# M7821.net
KiCad netlist of a schematic drawn in EAGLE
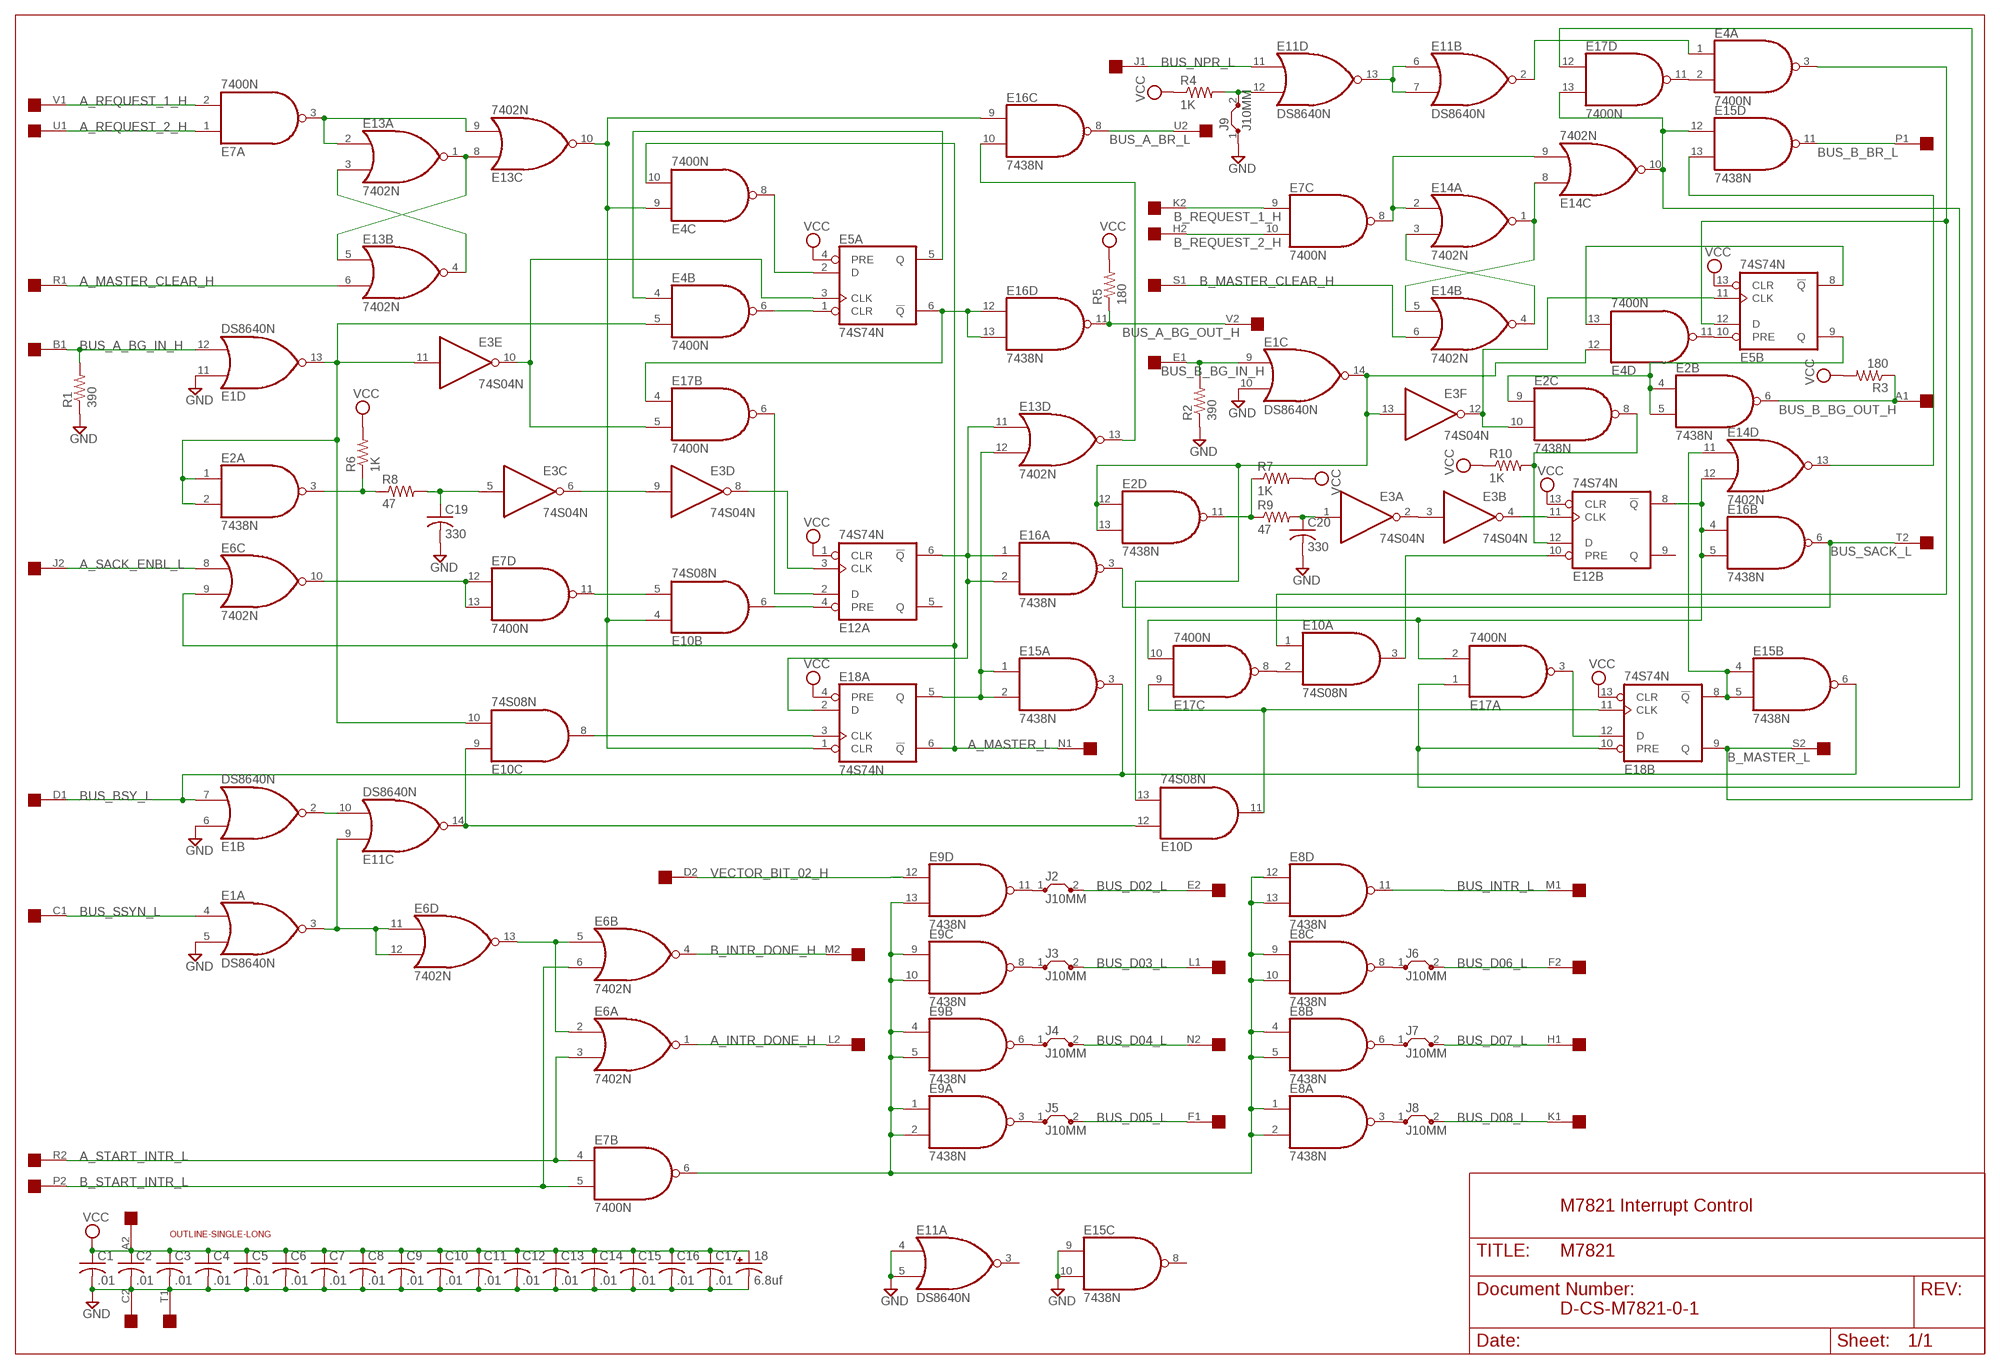
[diagram p0: schematic, sheet 1]

(export (version "E")
  (design (tool "Eeschema 10.0.6"))
  (components
    (comp (ref "18")
      (value "6.8uf")
      (footprint "eagle-import:E15-5")
      (libsource (lib "eagle-import") (part "CPOL-USE15-5AXIAL"))
    )
    (comp (ref "C1")
      (value ".01")
      (footprint "eagle-import:C050-025X075")
      (libsource (lib "eagle-import") (part "C-US050-025X075"))
    )
    (comp (ref "C2")
      (value ".01")
      (footprint "eagle-import:C050-025X075")
      (libsource (lib "eagle-import") (part "C-US050-025X075"))
    )
    (comp (ref "C3")
      (value ".01")
      (footprint "eagle-import:C050-025X075")
      (libsource (lib "eagle-import") (part "C-US050-025X075"))
    )
    (comp (ref "C4")
      (value ".01")
      (footprint "eagle-import:C050-025X075")
      (libsource (lib "eagle-import") (part "C-US050-025X075"))
    )
    (comp (ref "C5")
      (value ".01")
      (footprint "eagle-import:C050-025X075")
      (libsource (lib "eagle-import") (part "C-US050-025X075"))
    )
    (comp (ref "C6")
      (value ".01")
      (footprint "eagle-import:C050-025X075")
      (libsource (lib "eagle-import") (part "C-US050-025X075"))
    )
    (comp (ref "C7")
      (value ".01")
      (footprint "eagle-import:C050-025X075")
      (libsource (lib "eagle-import") (part "C-US050-025X075"))
    )
    (comp (ref "C8")
      (value ".01")
      (footprint "eagle-import:C050-025X075")
      (libsource (lib "eagle-import") (part "C-US050-025X075"))
    )
    (comp (ref "C9")
      (value ".01")
      (footprint "eagle-import:C050-025X075")
      (libsource (lib "eagle-import") (part "C-US050-025X075"))
    )
    (comp (ref "C10")
      (value ".01")
      (footprint "eagle-import:C050-025X075")
      (libsource (lib "eagle-import") (part "C-US050-025X075"))
    )
    (comp (ref "C11")
      (value ".01")
      (footprint "eagle-import:C050-025X075")
      (libsource (lib "eagle-import") (part "C-US050-025X075"))
    )
    (comp (ref "C12")
      (value ".01")
      (footprint "eagle-import:C050-025X075")
      (libsource (lib "eagle-import") (part "C-US050-025X075"))
    )
    (comp (ref "C13")
      (value ".01")
      (footprint "eagle-import:C050-025X075")
      (libsource (lib "eagle-import") (part "C-US050-025X075"))
    )
    (comp (ref "C14")
      (value ".01")
      (footprint "eagle-import:C050-025X075")
      (libsource (lib "eagle-import") (part "C-US050-025X075"))
    )
    (comp (ref "C15")
      (value ".01")
      (footprint "eagle-import:C050-025X075")
      (libsource (lib "eagle-import") (part "C-US050-025X075"))
    )
    (comp (ref "C16")
      (value ".01")
      (footprint "eagle-import:C050-025X075")
      (libsource (lib "eagle-import") (part "C-US050-025X075"))
    )
    (comp (ref "C17")
      (value ".01")
      (footprint "eagle-import:C050-025X075")
      (libsource (lib "eagle-import") (part "C-US050-025X075"))
    )
    (comp (ref "C19")
      (value "330")
      (footprint "eagle-import:C050-025X075")
      (libsource (lib "eagle-import") (part "C-US050-025X075"))
    )
    (comp (ref "C20")
      (value "330")
      (footprint "eagle-import:C050-025X075")
      (libsource (lib "eagle-import") (part "C-US050-025X075"))
    )
    (comp (ref "E1")
      (value "DS8640N")
      (footprint "eagle-import:DIL14")
      (libsource (lib "eagle-import") (part "DS8640N"))
    )
    (comp (ref "E2")
      (value "7438N")
      (footprint "eagle-import:DIL14")
      (libsource (lib "eagle-import") (part "7438N"))
    )
    (comp (ref "E3")
      (value "74S04N")
      (footprint "eagle-import:DIL14")
      (libsource (lib "eagle-import") (part "7404NS"))
    )
    (comp (ref "E4")
      (value "7400N")
      (footprint "eagle-import:DIL14")
      (libsource (lib "eagle-import") (part "7400N"))
    )
    (comp (ref "E5")
      (value "74S74N")
      (footprint "eagle-import:DIL14")
      (libsource (lib "eagle-import") (part "7474NS"))
    )
    (comp (ref "E6")
      (value "7402N")
      (footprint "eagle-import:DIL14")
      (libsource (lib "eagle-import") (part "7402N"))
    )
    (comp (ref "E7")
      (value "7400N")
      (footprint "eagle-import:DIL14")
      (libsource (lib "eagle-import") (part "7400N"))
    )
    (comp (ref "E8")
      (value "7438N")
      (footprint "eagle-import:DIL14")
      (libsource (lib "eagle-import") (part "7438N"))
    )
    (comp (ref "E9")
      (value "7438N")
      (footprint "eagle-import:DIL14")
      (libsource (lib "eagle-import") (part "7438N"))
    )
    (comp (ref "E10")
      (value "74S08N")
      (footprint "eagle-import:DIL14")
      (libsource (lib "eagle-import") (part "7408NS"))
    )
    (comp (ref "E11")
      (value "DS8640N")
      (footprint "eagle-import:DIL14")
      (libsource (lib "eagle-import") (part "DS8640N"))
    )
    (comp (ref "E12")
      (value "74S74N")
      (footprint "eagle-import:DIL14")
      (libsource (lib "eagle-import") (part "7474NS"))
    )
    (comp (ref "E13")
      (value "7402N")
      (footprint "eagle-import:DIL14")
      (libsource (lib "eagle-import") (part "7402N"))
    )
    (comp (ref "E14")
      (value "7402N")
      (footprint "eagle-import:DIL14")
      (libsource (lib "eagle-import") (part "7402N"))
    )
    (comp (ref "E15")
      (value "7438N")
      (footprint "eagle-import:DIL14")
      (libsource (lib "eagle-import") (part "7438N"))
    )
    (comp (ref "E16")
      (value "7438N")
      (footprint "eagle-import:DIL14")
      (libsource (lib "eagle-import") (part "7438N"))
    )
    (comp (ref "E17")
      (value "7400N")
      (footprint "eagle-import:DIL14")
      (libsource (lib "eagle-import") (part "7400N"))
    )
    (comp (ref "E18")
      (value "74S74N")
      (footprint "eagle-import:DIL14")
      (libsource (lib "eagle-import") (part "7474NS"))
    )
    (comp (ref "J2")
      (value "J10MM")
      (footprint "eagle-import:10")
      (libsource (lib "eagle-import") (part "J10MM"))
    )
    (comp (ref "J3")
      (value "J10MM")
      (footprint "eagle-import:10")
      (libsource (lib "eagle-import") (part "J10MM"))
    )
    (comp (ref "J4")
      (value "J10MM")
      (footprint "eagle-import:10")
      (libsource (lib "eagle-import") (part "J10MM"))
    )
    (comp (ref "J5")
      (value "J10MM")
      (footprint "eagle-import:10")
      (libsource (lib "eagle-import") (part "J10MM"))
    )
    (comp (ref "J6")
      (value "J10MM")
      (footprint "eagle-import:10")
      (libsource (lib "eagle-import") (part "J10MM"))
    )
    (comp (ref "J7")
      (value "J10MM")
      (footprint "eagle-import:10")
      (libsource (lib "eagle-import") (part "J10MM"))
    )
    (comp (ref "J8")
      (value "J10MM")
      (footprint "eagle-import:10")
      (libsource (lib "eagle-import") (part "J10MM"))
    )
    (comp (ref "J9")
      (value "J10MM")
      (footprint "eagle-import:10")
      (libsource (lib "eagle-import") (part "J10MM"))
    )
    (comp (ref "R1")
      (value "390")
      (footprint "eagle-import:0207_10")
      (libsource (lib "eagle-import") (part "R-US_0207/10"))
    )
    (comp (ref "R2")
      (value "390")
      (footprint "eagle-import:0207_10")
      (libsource (lib "eagle-import") (part "R-US_0207/10"))
    )
    (comp (ref "R3")
      (value "180")
      (footprint "eagle-import:0207_10")
      (libsource (lib "eagle-import") (part "R-US_0207/10"))
    )
    (comp (ref "R4")
      (value "1K")
      (footprint "eagle-import:0207_10")
      (libsource (lib "eagle-import") (part "R-US_0207/10"))
    )
    (comp (ref "R5")
      (value "180")
      (footprint "eagle-import:0207_10")
      (libsource (lib "eagle-import") (part "R-US_0207/10"))
    )
    (comp (ref "R6")
      (value "1K")
      (footprint "eagle-import:0207_10")
      (libsource (lib "eagle-import") (part "R-US_0207/10"))
    )
    (comp (ref "R7")
      (value "1K")
      (footprint "eagle-import:0207_10")
      (libsource (lib "eagle-import") (part "R-US_0207/10"))
    )
    (comp (ref "R8")
      (value "47")
      (footprint "eagle-import:0207_10")
      (libsource (lib "eagle-import") (part "R-US_0207/10"))
    )
    (comp (ref "R9")
      (value "47")
      (footprint "eagle-import:0207_10")
      (libsource (lib "eagle-import") (part "R-US_0207/10"))
    )
    (comp (ref "R10")
      (value "1K")
      (footprint "eagle-import:0207_10")
      (libsource (lib "eagle-import") (part "R-US_0207/10"))
    )
    (comp (ref "U$1")
      (value "OUTLINE-SINGLE-LONG")
      (footprint "eagle-import:SINGLE-LONG")
      (libsource (lib "eagle-import") (part "OUTLINE-SINGLE-LONG"))
    )
    (comp (ref "U$2")
      (value "SINGLE")
      (footprint "eagle-import:EDGE-CON2")
      (libsource (lib "eagle-import") (part "SINGLE"))
    )
  )
  (nets
    (net (code "1") (name "/A_INTR_DONE_H") (class "Default")
      (node (ref "E6") (pin "1") (pinfunction "O_1") (pintype "output"))
      (node (ref "U$2") (pin "L2") (pinfunction "1_L2") (pintype "bidirectional"))
    )
    (net (code "2") (name "/A_MASTER_CLEAR_H") (class "Default")
      (node (ref "E13") (pin "6") (pinfunction "I1_6") (pintype "input"))
      (node (ref "U$2") (pin "R1") (pinfunction "1_R1") (pintype "bidirectional"))
    )
    (net (code "3") (name "/A_MASTER_L") (class "Default")
      (node (ref "E18") (pin "6") (pinfunction "~{Q}_6") (pintype "output"))
      (node (ref "E4") (pin "10") (pinfunction "I1_10") (pintype "input"))
      (node (ref "E6") (pin "9") (pinfunction "I1_9") (pintype "input"))
      (node (ref "U$2") (pin "N1") (pinfunction "1_N1") (pintype "bidirectional"))
    )
    (net (code "4") (name "/A_REQUEST_1_H") (class "Default")
      (node (ref "E7") (pin "2") (pinfunction "I1_2") (pintype "input"))
      (node (ref "U$2") (pin "V1") (pinfunction "1_V1") (pintype "bidirectional"))
    )
    (net (code "5") (name "/A_REQUEST_2_H") (class "Default")
      (node (ref "E7") (pin "1") (pinfunction "I0_1") (pintype "input"))
      (node (ref "U$2") (pin "U1") (pinfunction "1_U1") (pintype "bidirectional"))
    )
    (net (code "6") (name "/A_SACK_ENBL_L") (class "Default")
      (node (ref "E6") (pin "8") (pinfunction "I0_8") (pintype "input"))
      (node (ref "U$2") (pin "J2") (pinfunction "1_J2") (pintype "bidirectional"))
    )
    (net (code "7") (name "/A_START_INTR_L") (class "Default")
      (node (ref "E6") (pin "3") (pinfunction "I1_3") (pintype "input"))
      (node (ref "E7") (pin "4") (pinfunction "I0_4") (pintype "input"))
      (node (ref "U$2") (pin "R2") (pinfunction "1_R2") (pintype "bidirectional"))
    )
    (net (code "8") (name "/BUS_A_BG_IN_H") (class "Default")
      (node (ref "E1") (pin "12") (pinfunction "I1_12") (pintype "input"))
      (node (ref "R1") (pin "2") (pinfunction "2_2") (pintype "passive"))
      (node (ref "U$2") (pin "B1") (pinfunction "1_B1") (pintype "bidirectional"))
    )
    (net (code "9") (name "/BUS_A_BG_OUT_H") (class "Default")
      (node (ref "E16") (pin "11") (pinfunction "O_11") (pintype "open_collector"))
      (node (ref "R5") (pin "1") (pinfunction "1_1") (pintype "passive"))
      (node (ref "U$2") (pin "V2") (pinfunction "1_V2") (pintype "bidirectional"))
    )
    (net (code "10") (name "/BUS_A_BR_L") (class "Default")
      (node (ref "E16") (pin "8") (pinfunction "O_8") (pintype "open_collector"))
      (node (ref "U$2") (pin "U2") (pinfunction "1_U2") (pintype "bidirectional"))
    )
    (net (code "11") (name "/BUS_BSY_L") (class "Default")
      (node (ref "E1") (pin "7") (pinfunction "I1_7") (pintype "input"))
      (node (ref "E15") (pin "3") (pinfunction "O_3") (pintype "open_collector"))
      (node (ref "E15") (pin "6") (pinfunction "O_6") (pintype "open_collector"))
      (node (ref "U$2") (pin "D1") (pinfunction "1_D1") (pintype "bidirectional"))
    )
    (net (code "12") (name "/BUS_B_BG_IN_H") (class "Default")
      (node (ref "E1") (pin "9") (pinfunction "I0_9") (pintype "input"))
      (node (ref "R2") (pin "2") (pinfunction "2_2") (pintype "passive"))
      (node (ref "U$2") (pin "E1") (pinfunction "1_E1") (pintype "bidirectional"))
    )
    (net (code "13") (name "/BUS_B_BG_OUT_H") (class "Default")
      (node (ref "E2") (pin "6") (pinfunction "O_6") (pintype "open_collector"))
      (node (ref "R3") (pin "1") (pinfunction "1_1") (pintype "passive"))
      (node (ref "U$2") (pin "A1") (pinfunction "1_A1") (pintype "bidirectional"))
    )
    (net (code "14") (name "/BUS_B_BR_L") (class "Default")
      (node (ref "E15") (pin "11") (pinfunction "O_11") (pintype "open_collector"))
      (node (ref "U$2") (pin "P1") (pinfunction "1_P1") (pintype "bidirectional"))
    )
    (net (code "15") (name "/BUS_D02_L") (class "Default")
      (node (ref "J2") (pin "2") (pinfunction "2_2") (pintype "passive"))
      (node (ref "U$2") (pin "E2") (pinfunction "1_E2") (pintype "bidirectional"))
    )
    (net (code "16") (name "/BUS_D03_L") (class "Default")
      (node (ref "J3") (pin "2") (pinfunction "2_2") (pintype "passive"))
      (node (ref "U$2") (pin "L1") (pinfunction "1_L1") (pintype "bidirectional"))
    )
    (net (code "17") (name "/BUS_D04_L") (class "Default")
      (node (ref "J4") (pin "2") (pinfunction "2_2") (pintype "passive"))
      (node (ref "U$2") (pin "N2") (pinfunction "1_N2") (pintype "bidirectional"))
    )
    (net (code "18") (name "/BUS_D05_L") (class "Default")
      (node (ref "J5") (pin "2") (pinfunction "2_2") (pintype "passive"))
      (node (ref "U$2") (pin "F1") (pinfunction "1_F1") (pintype "bidirectional"))
    )
    (net (code "19") (name "/BUS_D06_L") (class "Default")
      (node (ref "J6") (pin "2") (pinfunction "2_2") (pintype "passive"))
      (node (ref "U$2") (pin "F2") (pinfunction "1_F2") (pintype "bidirectional"))
    )
    (net (code "20") (name "/BUS_D07_L") (class "Default")
      (node (ref "J7") (pin "2") (pinfunction "2_2") (pintype "passive"))
      (node (ref "U$2") (pin "H1") (pinfunction "1_H1") (pintype "bidirectional"))
    )
    (net (code "21") (name "/BUS_D08_L") (class "Default")
      (node (ref "J8") (pin "2") (pinfunction "2_2") (pintype "passive"))
      (node (ref "U$2") (pin "K1") (pinfunction "1_K1") (pintype "bidirectional"))
    )
    (net (code "22") (name "/BUS_INTR_L") (class "Default")
      (node (ref "E8") (pin "11") (pinfunction "O_11") (pintype "open_collector"))
      (node (ref "U$2") (pin "M1") (pinfunction "1_M1") (pintype "bidirectional"))
    )
    (net (code "23") (name "/BUS_NPR_L") (class "Default")
      (node (ref "E11") (pin "11") (pinfunction "I0_11") (pintype "input"))
      (node (ref "U$2") (pin "J1") (pinfunction "1_J1") (pintype "bidirectional"))
    )
    (net (code "24") (name "/BUS_SACK_L") (class "Default")
      (node (ref "E16") (pin "3") (pinfunction "O_3") (pintype "open_collector"))
      (node (ref "E16") (pin "6") (pinfunction "O_6") (pintype "open_collector"))
      (node (ref "U$2") (pin "T2") (pinfunction "1_T2") (pintype "bidirectional"))
    )
    (net (code "25") (name "/BUS_SSYN_L") (class "Default")
      (node (ref "E1") (pin "4") (pinfunction "I0_4") (pintype "input"))
      (node (ref "U$2") (pin "C1") (pinfunction "1_C1") (pintype "bidirectional"))
    )
    (net (code "26") (name "/B_INTR_DONE_H") (class "Default")
      (node (ref "E6") (pin "4") (pinfunction "O_4") (pintype "output"))
      (node (ref "U$2") (pin "M2") (pinfunction "1_M2") (pintype "bidirectional"))
    )
    (net (code "27") (name "/B_MASTER_CLEAR_H") (class "Default")
      (node (ref "E14") (pin "6") (pinfunction "I1_6") (pintype "input"))
      (node (ref "U$2") (pin "S1") (pinfunction "1_S1") (pintype "bidirectional"))
    )
    (net (code "28") (name "/B_MASTER_L") (class "Default")
      (node (ref "E17") (pin "12") (pinfunction "I0_12") (pintype "input"))
      (node (ref "E18") (pin "9") (pinfunction "Q_9") (pintype "output"))
      (node (ref "U$2") (pin "S2") (pinfunction "1_S2") (pintype "bidirectional"))
    )
    (net (code "29") (name "/B_REQUEST_1_H") (class "Default")
      (node (ref "E7") (pin "9") (pinfunction "I0_9") (pintype "input"))
      (node (ref "U$2") (pin "K2") (pinfunction "1_K2") (pintype "bidirectional"))
    )
    (net (code "30") (name "/B_REQUEST_2_H") (class "Default")
      (node (ref "E7") (pin "10") (pinfunction "I1_10") (pintype "input"))
      (node (ref "U$2") (pin "H2") (pinfunction "1_H2") (pintype "bidirectional"))
    )
    (net (code "31") (name "/B_START_INTR_L") (class "Default")
      (node (ref "E6") (pin "6") (pinfunction "I1_6") (pintype "input"))
      (node (ref "E7") (pin "5") (pinfunction "I1_5") (pintype "input"))
      (node (ref "U$2") (pin "P2") (pinfunction "1_P2") (pintype "bidirectional"))
    )
    (net (code "32") (name "/VECTOR_BIT_02_H") (class "Default")
      (node (ref "E9") (pin "12") (pinfunction "I0_12") (pintype "input"))
      (node (ref "U$2") (pin "D2") (pinfunction "1_D2") (pintype "bidirectional"))
    )
    (net (code "33") (name "GND") (class "Default")
      (node (ref "18") (pin "-") (pinfunction "-_-") (pintype "passive"))
      (node (ref "C1") (pin "2") (pinfunction "2_2") (pintype "passive"))
      (node (ref "C10") (pin "2") (pinfunction "2_2") (pintype "passive"))
      (node (ref "C11") (pin "2") (pinfunction "2_2") (pintype "passive"))
      (node (ref "C12") (pin "2") (pinfunction "2_2") (pintype "passive"))
      (node (ref "C13") (pin "2") (pinfunction "2_2") (pintype "passive"))
      (node (ref "C14") (pin "2") (pinfunction "2_2") (pintype "passive"))
      (node (ref "C15") (pin "2") (pinfunction "2_2") (pintype "passive"))
      (node (ref "C16") (pin "2") (pinfunction "2_2") (pintype "passive"))
      (node (ref "C17") (pin "2") (pinfunction "2_2") (pintype "passive"))
      (node (ref "C19") (pin "2") (pinfunction "2_2") (pintype "passive"))
      (node (ref "C2") (pin "2") (pinfunction "2_2") (pintype "passive"))
      (node (ref "C20") (pin "2") (pinfunction "2_2") (pintype "passive"))
      (node (ref "C3") (pin "2") (pinfunction "2_2") (pintype "passive"))
      (node (ref "C4") (pin "2") (pinfunction "2_2") (pintype "passive"))
      (node (ref "C5") (pin "2") (pinfunction "2_2") (pintype "passive"))
      (node (ref "C6") (pin "2") (pinfunction "2_2") (pintype "passive"))
      (node (ref "C7") (pin "2") (pinfunction "2_2") (pintype "passive"))
      (node (ref "C8") (pin "2") (pinfunction "2_2") (pintype "passive"))
      (node (ref "C9") (pin "2") (pinfunction "2_2") (pintype "passive"))
      (node (ref "E1") (pin "10") (pinfunction "I1_10") (pintype "input"))
      (node (ref "E1") (pin "11") (pinfunction "I0_11") (pintype "input"))
      (node (ref "E1") (pin "5") (pinfunction "I1_5") (pintype "input"))
      (node (ref "E1") (pin "6") (pinfunction "I0_6") (pintype "input"))
      (node (ref "E11") (pin "4") (pinfunction "I0_4") (pintype "input"))
      (node (ref "E11") (pin "5") (pinfunction "I1_5") (pintype "input"))
      (node (ref "E15") (pin "10") (pinfunction "I1_10") (pintype "input"))
      (node (ref "E15") (pin "9") (pinfunction "I0_9") (pintype "input"))
      (node (ref "J9") (pin "1") (pinfunction "1_1") (pintype "passive"))
      (node (ref "R1") (pin "1") (pinfunction "1_1") (pintype "passive"))
      (node (ref "R2") (pin "1") (pinfunction "1_1") (pintype "passive"))
      (node (ref "U$2") (pin "C2") (pinfunction "1_C2") (pintype "bidirectional"))
      (node (ref "U$2") (pin "T1") (pinfunction "1_T1") (pintype "bidirectional"))
    )
    (net (code "34") (name "Net-(E2A-O)") (class "Default")
      (node (ref "E2") (pin "3") (pinfunction "O_3") (pintype "open_collector"))
      (node (ref "R6") (pin "1") (pinfunction "1_1") (pintype "passive"))
      (node (ref "R8") (pin "1") (pinfunction "1_1") (pintype "passive"))
    )
    (net (code "35") (name "Net-(E2B-I0)") (class "Default")
      (node (ref "E2") (pin "4") (pinfunction "I0_4") (pintype "input"))
      (node (ref "E2") (pin "5") (pinfunction "I1_5") (pintype "input"))
      (node (ref "E2") (pin "9") (pinfunction "I0_9") (pintype "input"))
      (node (ref "E5") (pin "9") (pinfunction "Q_9") (pintype "output"))
    )
    (net (code "36") (name "Net-(E2C-I1)") (class "Default")
      (node (ref "E2") (pin "10") (pinfunction "I1_10") (pintype "input"))
      (node (ref "E3") (pin "12") (pinfunction "O_12") (pintype "output"))
      (node (ref "E5") (pin "11") (pinfunction "CLK_11") (pintype "input"))
    )
    (net (code "37") (name "Net-(E2D-O)") (class "Default")
      (node (ref "E2") (pin "11") (pinfunction "O_11") (pintype "open_collector"))
      (node (ref "R7") (pin "1") (pinfunction "1_1") (pintype "passive"))
      (node (ref "R9") (pin "1") (pinfunction "1_1") (pintype "passive"))
    )
    (net (code "38") (name "Net-(E3A-I)") (class "Default")
      (node (ref "C20") (pin "1") (pinfunction "1_1") (pintype "passive"))
      (node (ref "E3") (pin "1") (pinfunction "I_1") (pintype "input"))
      (node (ref "R9") (pin "2") (pinfunction "2_2") (pintype "passive"))
    )
    (net (code "39") (name "Net-(E3A-O)") (class "Default")
      (node (ref "E3") (pin "2") (pinfunction "O_2") (pintype "output"))
      (node (ref "E3") (pin "3") (pinfunction "I_3") (pintype "input"))
    )
    (net (code "40") (name "Net-(E3C-I)") (class "Default")
      (node (ref "C19") (pin "1") (pinfunction "1_1") (pintype "passive"))
      (node (ref "E3") (pin "5") (pinfunction "I_5") (pintype "input"))
      (node (ref "R8") (pin "2") (pinfunction "2_2") (pintype "passive"))
    )
    (net (code "41") (name "Net-(E3C-O)") (class "Default")
      (node (ref "E3") (pin "6") (pinfunction "O_6") (pintype "output"))
      (node (ref "E3") (pin "9") (pinfunction "I_9") (pintype "input"))
    )
    (net (code "42") (name "Net-(E4B-I0)") (class "Default")
      (node (ref "E4") (pin "4") (pinfunction "I0_4") (pintype "input"))
      (node (ref "E5") (pin "5") (pinfunction "Q_5") (pintype "output"))
    )
    (net (code "43") (name "Net-(E4B-O)") (class "Default")
      (node (ref "E4") (pin "6") (pinfunction "O_6") (pintype "output"))
      (node (ref "E5") (pin "1") (pinfunction "CLR_1") (pintype "input"))
    )
    (net (code "44") (name "Net-(E4C-O)") (class "Default")
      (node (ref "E4") (pin "8") (pinfunction "O_8") (pintype "output"))
      (node (ref "E5") (pin "2") (pinfunction "D_2") (pintype "input"))
    )
    (net (code "45") (name "Net-(E4D-I1)") (class "Default")
      (node (ref "E4") (pin "13") (pinfunction "I1_13") (pintype "input"))
      (node (ref "E5") (pin "8") (pinfunction "~{Q}_8") (pintype "output"))
    )
    (net (code "46") (name "Net-(E4D-O)") (class "Default")
      (node (ref "E4") (pin "11") (pinfunction "O_11") (pintype "output"))
      (node (ref "E5") (pin "10") (pinfunction "PRE_10") (pintype "input"))
    )
    (net (code "47") (name "Net-(E6A-I0)") (class "Default")
      (node (ref "E6") (pin "13") (pinfunction "O_13") (pintype "output"))
      (node (ref "E6") (pin "2") (pinfunction "I0_2") (pintype "input"))
      (node (ref "E6") (pin "5") (pinfunction "I0_5") (pintype "input"))
    )
    (net (code "48") (name "Net-(E6C-O)") (class "Default")
      (node (ref "E6") (pin "10") (pinfunction "O_10") (pintype "output"))
      (node (ref "E7") (pin "12") (pinfunction "I0_12") (pintype "input"))
      (node (ref "E7") (pin "13") (pinfunction "I1_13") (pintype "input"))
    )
    (net (code "49") (name "Net-(E7B-O)") (class "Default")
      (node (ref "E7") (pin "6") (pinfunction "O_6") (pintype "output"))
      (node (ref "E8") (pin "1") (pinfunction "I0_1") (pintype "input"))
      (node (ref "E8") (pin "10") (pinfunction "I1_10") (pintype "input"))
      (node (ref "E8") (pin "12") (pinfunction "I0_12") (pintype "input"))
      (node (ref "E8") (pin "13") (pinfunction "I1_13") (pintype "input"))
      (node (ref "E8") (pin "2") (pinfunction "I1_2") (pintype "input"))
      (node (ref "E8") (pin "4") (pinfunction "I0_4") (pintype "input"))
      (node (ref "E8") (pin "5") (pinfunction "I1_5") (pintype "input"))
      (node (ref "E8") (pin "9") (pinfunction "I0_9") (pintype "input"))
      (node (ref "E9") (pin "1") (pinfunction "I0_1") (pintype "input"))
      (node (ref "E9") (pin "10") (pinfunction "I1_10") (pintype "input"))
      (node (ref "E9") (pin "13") (pinfunction "I1_13") (pintype "input"))
      (node (ref "E9") (pin "2") (pinfunction "I1_2") (pintype "input"))
      (node (ref "E9") (pin "4") (pinfunction "I0_4") (pintype "input"))
      (node (ref "E9") (pin "5") (pinfunction "I1_5") (pintype "input"))
      (node (ref "E9") (pin "9") (pinfunction "I0_9") (pintype "input"))
    )
    (net (code "50") (name "Net-(E8A-O)") (class "Default")
      (node (ref "E8") (pin "3") (pinfunction "O_3") (pintype "open_collector"))
      (node (ref "J8") (pin "1") (pinfunction "1_1") (pintype "passive"))
    )
    (net (code "51") (name "Net-(E8B-O)") (class "Default")
      (node (ref "E8") (pin "6") (pinfunction "O_6") (pintype "open_collector"))
      (node (ref "J7") (pin "1") (pinfunction "1_1") (pintype "passive"))
    )
    (net (code "52") (name "Net-(E8C-O)") (class "Default")
      (node (ref "E8") (pin "8") (pinfunction "O_8") (pintype "open_collector"))
      (node (ref "J6") (pin "1") (pinfunction "1_1") (pintype "passive"))
    )
    (net (code "53") (name "Net-(E9A-O)") (class "Default")
      (node (ref "E9") (pin "3") (pinfunction "O_3") (pintype "open_collector"))
      (node (ref "J5") (pin "1") (pinfunction "1_1") (pintype "passive"))
    )
    (net (code "54") (name "Net-(E9B-O)") (class "Default")
      (node (ref "E9") (pin "6") (pinfunction "O_6") (pintype "open_collector"))
      (node (ref "J4") (pin "1") (pinfunction "1_1") (pintype "passive"))
    )
    (net (code "55") (name "Net-(E9C-O)") (class "Default")
      (node (ref "E9") (pin "8") (pinfunction "O_8") (pintype "open_collector"))
      (node (ref "J3") (pin "1") (pinfunction "1_1") (pintype "passive"))
    )
    (net (code "56") (name "Net-(E9D-O)") (class "Default")
      (node (ref "E9") (pin "11") (pinfunction "O_11") (pintype "open_collector"))
      (node (ref "J2") (pin "1") (pinfunction "1_1") (pintype "passive"))
    )
    (net (code "57") (name "Net-(E10A-I0)") (class "Default")
      (node (ref "E10") (pin "1") (pinfunction "I0_1") (pintype "input"))
      (node (ref "E4") (pin "3") (pinfunction "O_3") (pintype "output"))
      (node (ref "E5") (pin "12") (pinfunction "D_12") (pintype "input"))
    )
    (net (code "58") (name "Net-(E10A-I1)") (class "Default")
      (node (ref "E10") (pin "2") (pinfunction "I1_2") (pintype "input"))
      (node (ref "E17") (pin "8") (pinfunction "O_8") (pintype "output"))
    )
    (net (code "59") (name "Net-(E10A-O)") (class "Default")
      (node (ref "E10") (pin "3") (pinfunction "O_3") (pintype "output"))
      (node (ref "E12") (pin "10") (pinfunction "PRE_10") (pintype "input"))
    )
    (net (code "60") (name "Net-(E10B-I0)") (class "Default")
      (node (ref "E10") (pin "4") (pinfunction "I0_4") (pintype "input"))
      (node (ref "E13") (pin "10") (pinfunction "O_10") (pintype "output"))
      (node (ref "E16") (pin "9") (pinfunction "I0_9") (pintype "input"))
      (node (ref "E18") (pin "1") (pinfunction "CLR_1") (pintype "input"))
      (node (ref "E4") (pin "9") (pinfunction "I0_9") (pintype "input"))
    )
    (net (code "61") (name "Net-(E10B-I1)") (class "Default")
      (node (ref "E10") (pin "5") (pinfunction "I1_5") (pintype "input"))
      (node (ref "E7") (pin "11") (pinfunction "O_11") (pintype "output"))
    )
    (net (code "62") (name "Net-(E10B-O)") (class "Default")
      (node (ref "E10") (pin "6") (pinfunction "O_6") (pintype "output"))
      (node (ref "E12") (pin "4") (pinfunction "PRE_4") (pintype "input"))
    )
    (net (code "63") (name "Net-(E10C-I0)") (class "Default")
      (node (ref "E10") (pin "12") (pinfunction "I0_12") (pintype "input"))
      (node (ref "E10") (pin "9") (pinfunction "I0_9") (pintype "input"))
      (node (ref "E11") (pin "14") (pinfunction "O_14") (pintype "output"))
    )
    (net (code "64") (name "Net-(E10C-I1)") (class "Default")
      (node (ref "E1") (pin "13") (pinfunction "O_13") (pintype "output"))
      (node (ref "E10") (pin "10") (pinfunction "I1_10") (pintype "input"))
      (node (ref "E2") (pin "1") (pinfunction "I0_1") (pintype "input"))
      (node (ref "E2") (pin "2") (pinfunction "I1_2") (pintype "input"))
      (node (ref "E3") (pin "11") (pinfunction "I_11") (pintype "input"))
      (node (ref "E4") (pin "5") (pinfunction "I1_5") (pintype "input"))
    )
    (net (code "65") (name "Net-(E10C-O)") (class "Default")
      (node (ref "E10") (pin "8") (pinfunction "O_8") (pintype "output"))
      (node (ref "E18") (pin "3") (pinfunction "CLK_3") (pintype "input"))
    )
    (net (code "66") (name "Net-(E10D-I1)") (class "Default")
      (node (ref "E1") (pin "14") (pinfunction "O_14") (pintype "output"))
      (node (ref "E10") (pin "13") (pinfunction "I1_13") (pintype "input"))
      (node (ref "E2") (pin "12") (pinfunction "I0_12") (pintype "input"))
      (node (ref "E2") (pin "13") (pinfunction "I1_13") (pintype "input"))
      (node (ref "E3") (pin "13") (pinfunction "I_13") (pintype "input"))
      (node (ref "E4") (pin "12") (pinfunction "I0_12") (pintype "input"))
    )
    (net (code "67") (name "Net-(E10D-O)") (class "Default")
      (node (ref "E10") (pin "11") (pinfunction "O_11") (pintype "output"))
      (node (ref "E17") (pin "9") (pinfunction "I0_9") (pintype "input"))
      (node (ref "E18") (pin "11") (pinfunction "CLK_11") (pintype "input"))
    )
    (net (code "68") (name "Net-(E11B-I0)") (class "Default")
      (node (ref "E11") (pin "13") (pinfunction "O_13") (pintype "output"))
      (node (ref "E11") (pin "6") (pinfunction "I0_6") (pintype "input"))
      (node (ref "E11") (pin "7") (pinfunction "I1_7") (pintype "input"))
    )
    (net (code "69") (name "Net-(E11B-O)") (class "Default")
      (node (ref "E11") (pin "2") (pinfunction "O_2") (pintype "output"))
      (node (ref "E4") (pin "1") (pinfunction "I0_1") (pintype "input"))
    )
    (net (code "70") (name "Net-(E11C-I0)") (class "Default")
      (node (ref "E1") (pin "3") (pinfunction "O_3") (pintype "output"))
      (node (ref "E11") (pin "9") (pinfunction "I0_9") (pintype "input"))
      (node (ref "E6") (pin "11") (pinfunction "I0_11") (pintype "input"))
      (node (ref "E6") (pin "12") (pinfunction "I1_12") (pintype "input"))
    )
    (net (code "71") (name "Net-(E11C-I1)") (class "Default")
      (node (ref "E1") (pin "2") (pinfunction "O_2") (pintype "output"))
      (node (ref "E11") (pin "10") (pinfunction "I1_10") (pintype "input"))
    )
    (net (code "72") (name "Net-(E11D-I1)") (class "Default")
      (node (ref "E11") (pin "12") (pinfunction "I1_12") (pintype "input"))
      (node (ref "J9") (pin "2") (pinfunction "2_2") (pintype "passive"))
      (node (ref "R4") (pin "2") (pinfunction "2_2") (pintype "passive"))
    )
    (net (code "73") (name "Net-(E12A-CLK)") (class "Default")
      (node (ref "E12") (pin "3") (pinfunction "CLK_3") (pintype "input"))
      (node (ref "E3") (pin "8") (pinfunction "O_8") (pintype "output"))
    )
    (net (code "74") (name "Net-(E12A-D)") (class "Default")
      (node (ref "E12") (pin "2") (pinfunction "D_2") (pintype "input"))
      (node (ref "E17") (pin "6") (pinfunction "O_6") (pintype "output"))
    )
    (net (code "75") (name "Net-(E12A-~{Q})") (class "Default")
      (node (ref "E12") (pin "6") (pinfunction "~{Q}_6") (pintype "output"))
      (node (ref "E13") (pin "11") (pinfunction "I0_11") (pintype "input"))
      (node (ref "E16") (pin "1") (pinfunction "I0_1") (pintype "input"))
      (node (ref "E16") (pin "2") (pinfunction "I1_2") (pintype "input"))
      (node (ref "E18") (pin "2") (pinfunction "D_2") (pintype "input"))
    )
    (net (code "76") (name "Net-(E12B-CLK)") (class "Default")
      (node (ref "E12") (pin "11") (pinfunction "CLK_11") (pintype "input"))
      (node (ref "E3") (pin "4") (pinfunction "O_4") (pintype "output"))
    )
    (net (code "77") (name "Net-(E12B-D)") (class "Default")
      (node (ref "E12") (pin "12") (pinfunction "D_12") (pintype "input"))
      (node (ref "E2") (pin "8") (pinfunction "O_8") (pintype "open_collector"))
      (node (ref "R10") (pin "2") (pinfunction "2_2") (pintype "passive"))
    )
    (net (code "78") (name "Net-(E12B-~{Q})") (class "Default")
      (node (ref "E12") (pin "8") (pinfunction "~{Q}_8") (pintype "output"))
      (node (ref "E14") (pin "12") (pinfunction "I1_12") (pintype "input"))
      (node (ref "E16") (pin "4") (pinfunction "I0_4") (pintype "input"))
      (node (ref "E16") (pin "5") (pinfunction "I1_5") (pintype "input"))
      (node (ref "E17") (pin "10") (pinfunction "I1_10") (pintype "input"))
      (node (ref "E17") (pin "2") (pinfunction "I1_2") (pintype "input"))
    )
    (net (code "79") (name "Net-(E13A-I0)") (class "Default")
      (node (ref "E13") (pin "2") (pinfunction "I0_2") (pintype "input"))
      (node (ref "E13") (pin "9") (pinfunction "I1_9") (pintype "input"))
      (node (ref "E7") (pin "3") (pinfunction "O_3") (pintype "output"))
    )
    (net (code "80") (name "Net-(E13A-I1)") (class "Default")
      (node (ref "E13") (pin "3") (pinfunction "I1_3") (pintype "input"))
      (node (ref "E13") (pin "4") (pinfunction "O_4") (pintype "output"))
    )
    (net (code "81") (name "Net-(E13A-O)") (class "Default")
      (node (ref "E13") (pin "1") (pinfunction "O_1") (pintype "output"))
      (node (ref "E13") (pin "5") (pinfunction "I0_5") (pintype "input"))
      (node (ref "E13") (pin "8") (pinfunction "I0_8") (pintype "input"))
    )
    (net (code "82") (name "Net-(E13D-I1)") (class "Default")
      (node (ref "E13") (pin "12") (pinfunction "I1_12") (pintype "input"))
      (node (ref "E15") (pin "1") (pinfunction "I0_1") (pintype "input"))
      (node (ref "E15") (pin "2") (pinfunction "I1_2") (pintype "input"))
      (node (ref "E18") (pin "5") (pinfunction "Q_5") (pintype "output"))
    )
    (net (code "83") (name "Net-(E13D-O)") (class "Default")
      (node (ref "E13") (pin "13") (pinfunction "O_13") (pintype "output"))
      (node (ref "E16") (pin "10") (pinfunction "I1_10") (pintype "input"))
    )
    (net (code "84") (name "Net-(E14A-I0)") (class "Default")
      (node (ref "E14") (pin "2") (pinfunction "I0_2") (pintype "input"))
      (node (ref "E14") (pin "9") (pinfunction "I1_9") (pintype "input"))
      (node (ref "E7") (pin "8") (pinfunction "O_8") (pintype "output"))
    )
    (net (code "85") (name "Net-(E14A-I1)") (class "Default")
      (node (ref "E14") (pin "3") (pinfunction "I1_3") (pintype "input"))
      (node (ref "E14") (pin "4") (pinfunction "O_4") (pintype "output"))
    )
    (net (code "86") (name "Net-(E14A-O)") (class "Default")
      (node (ref "E14") (pin "1") (pinfunction "O_1") (pintype "output"))
      (node (ref "E14") (pin "5") (pinfunction "I0_5") (pintype "input"))
      (node (ref "E14") (pin "8") (pinfunction "I0_8") (pintype "input"))
    )
    (net (code "87") (name "Net-(E14C-O)") (class "Default")
      (node (ref "E14") (pin "10") (pinfunction "O_10") (pintype "output"))
      (node (ref "E15") (pin "12") (pinfunction "I0_12") (pintype "input"))
      (node (ref "E17") (pin "1") (pinfunction "I0_1") (pintype "input"))
      (node (ref "E17") (pin "13") (pinfunction "I1_13") (pintype "input"))
      (node (ref "E18") (pin "10") (pinfunction "PRE_10") (pintype "input"))
    )
    (net (code "88") (name "Net-(E14D-I0)") (class "Default")
      (node (ref "E14") (pin "11") (pinfunction "I0_11") (pintype "input"))
      (node (ref "E15") (pin "4") (pinfunction "I0_4") (pintype "input"))
      (node (ref "E15") (pin "5") (pinfunction "I1_5") (pintype "input"))
      (node (ref "E18") (pin "8") (pinfunction "~{Q}_8") (pintype "output"))
    )
    (net (code "89") (name "Net-(E14D-O)") (class "Default")
      (node (ref "E14") (pin "13") (pinfunction "O_13") (pintype "output"))
      (node (ref "E15") (pin "13") (pinfunction "I1_13") (pintype "input"))
    )
    (net (code "90") (name "Net-(E16D-I0)") (class "Default")
      (node (ref "E16") (pin "12") (pinfunction "I0_12") (pintype "input"))
      (node (ref "E16") (pin "13") (pinfunction "I1_13") (pintype "input"))
      (node (ref "E17") (pin "4") (pinfunction "I0_4") (pintype "input"))
      (node (ref "E5") (pin "6") (pinfunction "~{Q}_6") (pintype "output"))
    )
    (net (code "91") (name "Net-(E17A-O)") (class "Default")
      (node (ref "E17") (pin "3") (pinfunction "O_3") (pintype "output"))
      (node (ref "E18") (pin "12") (pinfunction "D_12") (pintype "input"))
    )
    (net (code "92") (name "Net-(E17B-I1)") (class "Default")
      (node (ref "E17") (pin "5") (pinfunction "I1_5") (pintype "input"))
      (node (ref "E3") (pin "10") (pinfunction "O_10") (pintype "output"))
      (node (ref "E5") (pin "3") (pinfunction "CLK_3") (pintype "input"))
    )
    (net (code "93") (name "Net-(E17D-O)") (class "Default")
      (node (ref "E17") (pin "11") (pinfunction "O_11") (pintype "output"))
      (node (ref "E4") (pin "2") (pinfunction "I1_2") (pintype "input"))
    )
    (net (code "94") (name "VCC") (class "Default")
      (node (ref "18") (pin "+") (pinfunction "+_+") (pintype "passive"))
      (node (ref "C1") (pin "1") (pinfunction "1_1") (pintype "passive"))
      (node (ref "C10") (pin "1") (pinfunction "1_1") (pintype "passive"))
      (node (ref "C11") (pin "1") (pinfunction "1_1") (pintype "passive"))
      (node (ref "C12") (pin "1") (pinfunction "1_1") (pintype "passive"))
      (node (ref "C13") (pin "1") (pinfunction "1_1") (pintype "passive"))
      (node (ref "C14") (pin "1") (pinfunction "1_1") (pintype "passive"))
      (node (ref "C15") (pin "1") (pinfunction "1_1") (pintype "passive"))
      (node (ref "C16") (pin "1") (pinfunction "1_1") (pintype "passive"))
      (node (ref "C17") (pin "1") (pinfunction "1_1") (pintype "passive"))
      (node (ref "C2") (pin "1") (pinfunction "1_1") (pintype "passive"))
      (node (ref "C3") (pin "1") (pinfunction "1_1") (pintype "passive"))
      (node (ref "C4") (pin "1") (pinfunction "1_1") (pintype "passive"))
      (node (ref "C5") (pin "1") (pinfunction "1_1") (pintype "passive"))
      (node (ref "C6") (pin "1") (pinfunction "1_1") (pintype "passive"))
      (node (ref "C7") (pin "1") (pinfunction "1_1") (pintype "passive"))
      (node (ref "C8") (pin "1") (pinfunction "1_1") (pintype "passive"))
      (node (ref "C9") (pin "1") (pinfunction "1_1") (pintype "passive"))
      (node (ref "E12") (pin "1") (pinfunction "CLR_1") (pintype "input"))
      (node (ref "E12") (pin "13") (pinfunction "CLR_13") (pintype "input"))
      (node (ref "E18") (pin "13") (pinfunction "CLR_13") (pintype "input"))
      (node (ref "E18") (pin "4") (pinfunction "PRE_4") (pintype "input"))
      (node (ref "E5") (pin "13") (pinfunction "CLR_13") (pintype "input"))
      (node (ref "E5") (pin "4") (pinfunction "PRE_4") (pintype "input"))
      (node (ref "R10") (pin "1") (pinfunction "1_1") (pintype "passive"))
      (node (ref "R3") (pin "2") (pinfunction "2_2") (pintype "passive"))
      (node (ref "R4") (pin "1") (pinfunction "1_1") (pintype "passive"))
      (node (ref "R5") (pin "2") (pinfunction "2_2") (pintype "passive"))
      (node (ref "R6") (pin "2") (pinfunction "2_2") (pintype "passive"))
      (node (ref "R7") (pin "2") (pinfunction "2_2") (pintype "passive"))
      (node (ref "U$2") (pin "A2") (pinfunction "1_A2") (pintype "bidirectional"))
    )
    (net (code "95") (name "unconnected-(E11A-O-Pad3)") (class "Default")
      (node (ref "E11") (pin "3") (pinfunction "O_3") (pintype "output"))
    )
    (net (code "96") (name "unconnected-(E12A-Q-Pad5)") (class "Default")
      (node (ref "E12") (pin "5") (pinfunction "Q_5") (pintype "output"))
    )
    (net (code "97") (name "unconnected-(E12B-Q-Pad9)") (class "Default")
      (node (ref "E12") (pin "9") (pinfunction "Q_9") (pintype "output"))
    )
    (net (code "98") (name "unconnected-(E15C-O-Pad8)") (class "Default")
      (node (ref "E15") (pin "8") (pinfunction "O_8") (pintype "open_collector"))
    )
  )
)
